# sensor_board.net
KiCad netlist of a schematic drawn in EAGLE
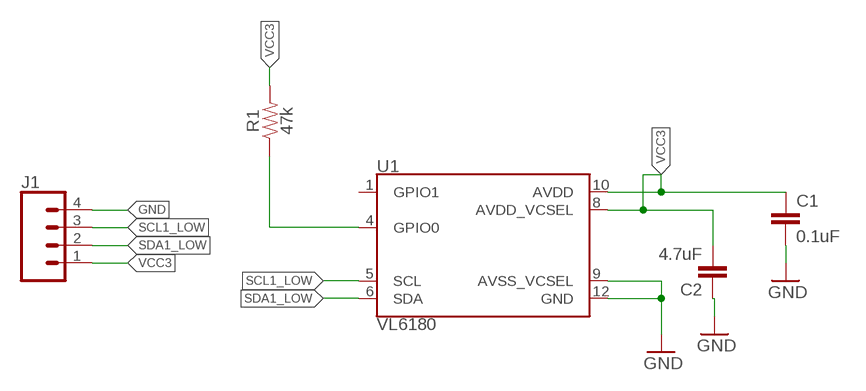
[diagram p0: schematic, sheet 1]

(export (version "E")
  (design (tool "Eeschema 10.0.6"))
  (components
    (comp (ref "C1")
      (value "0.1uF")
      (footprint "eagle-import:0603")
      (libsource (lib "eagle-import") (part "0.1UF-0603-25V-(+80/-20%)"))
    )
    (comp (ref "C2")
      (value "4.7uF")
      (footprint "eagle-import:0603")
      (libsource (lib "eagle-import") (part "4.7UF-0603-6.3V-(10%)"))
    )
    (comp (ref "J1")
      (value "CONN_04PTH")
      (footprint "eagle-import:1X04")
      (libsource (lib "eagle-import") (part "CONN_04PTH"))
    )
    (comp (ref "R1")
      (value "47k")
      (footprint "eagle-import:0603")
      (libsource (lib "eagle-import") (part "47KOHM-0603-1/10W-1%"))
    )
    (comp (ref "U1")
      (value "VL6180")
      (footprint "eagle-import:VL6180")
      (libsource (lib "eagle-import") (part "VL6180"))
    )
  )
  (nets
    (net (code "1") (name "GND") (class "Default")
      (node (ref "C1") (pin "2") (pinfunction "2_2") (pintype "passive"))
      (node (ref "C2") (pin "1") (pinfunction "1_1") (pintype "passive"))
      (node (ref "J1") (pin "4") (pinfunction "4_4") (pintype "passive"))
      (node (ref "U1") (pin "12") (pinfunction "GND_12") (pintype "bidirectional"))
      (node (ref "U1") (pin "9") (pinfunction "AVSS_VCSEL_9") (pintype "bidirectional"))
    )
    (net (code "2") (name "Net-(U1-GPIO0)") (class "Default")
      (node (ref "R1") (pin "1") (pinfunction "1_1") (pintype "passive"))
      (node (ref "U1") (pin "4") (pinfunction "GPIO0_4") (pintype "bidirectional"))
    )
    (net (code "3") (name "SCL1_LOW") (class "Default")
      (node (ref "J1") (pin "3") (pinfunction "3_3") (pintype "passive"))
      (node (ref "U1") (pin "5") (pinfunction "SCL_5") (pintype "bidirectional"))
    )
    (net (code "4") (name "SDA1_LOW") (class "Default")
      (node (ref "J1") (pin "2") (pinfunction "2_2") (pintype "passive"))
      (node (ref "U1") (pin "6") (pinfunction "SDA_6") (pintype "bidirectional"))
    )
    (net (code "5") (name "VCC3") (class "Default")
      (node (ref "C1") (pin "1") (pinfunction "1_1") (pintype "passive"))
      (node (ref "C2") (pin "2") (pinfunction "2_2") (pintype "passive"))
      (node (ref "J1") (pin "1") (pinfunction "1_1") (pintype "passive"))
      (node (ref "R1") (pin "2") (pinfunction "2_2") (pintype "passive"))
      (node (ref "U1") (pin "10") (pinfunction "AVDD_10") (pintype "bidirectional"))
      (node (ref "U1") (pin "8") (pinfunction "AVDD_VCSEL_8") (pintype "bidirectional"))
    )
    (net (code "6") (name "unconnected-(U1-GPIO1-Pad1)") (class "Default")
      (node (ref "U1") (pin "1") (pinfunction "GPIO1_1") (pintype "bidirectional"))
    )
  )
)
